# Sheet2.net
KiCad netlist of a schematic drawn in Altium Designer
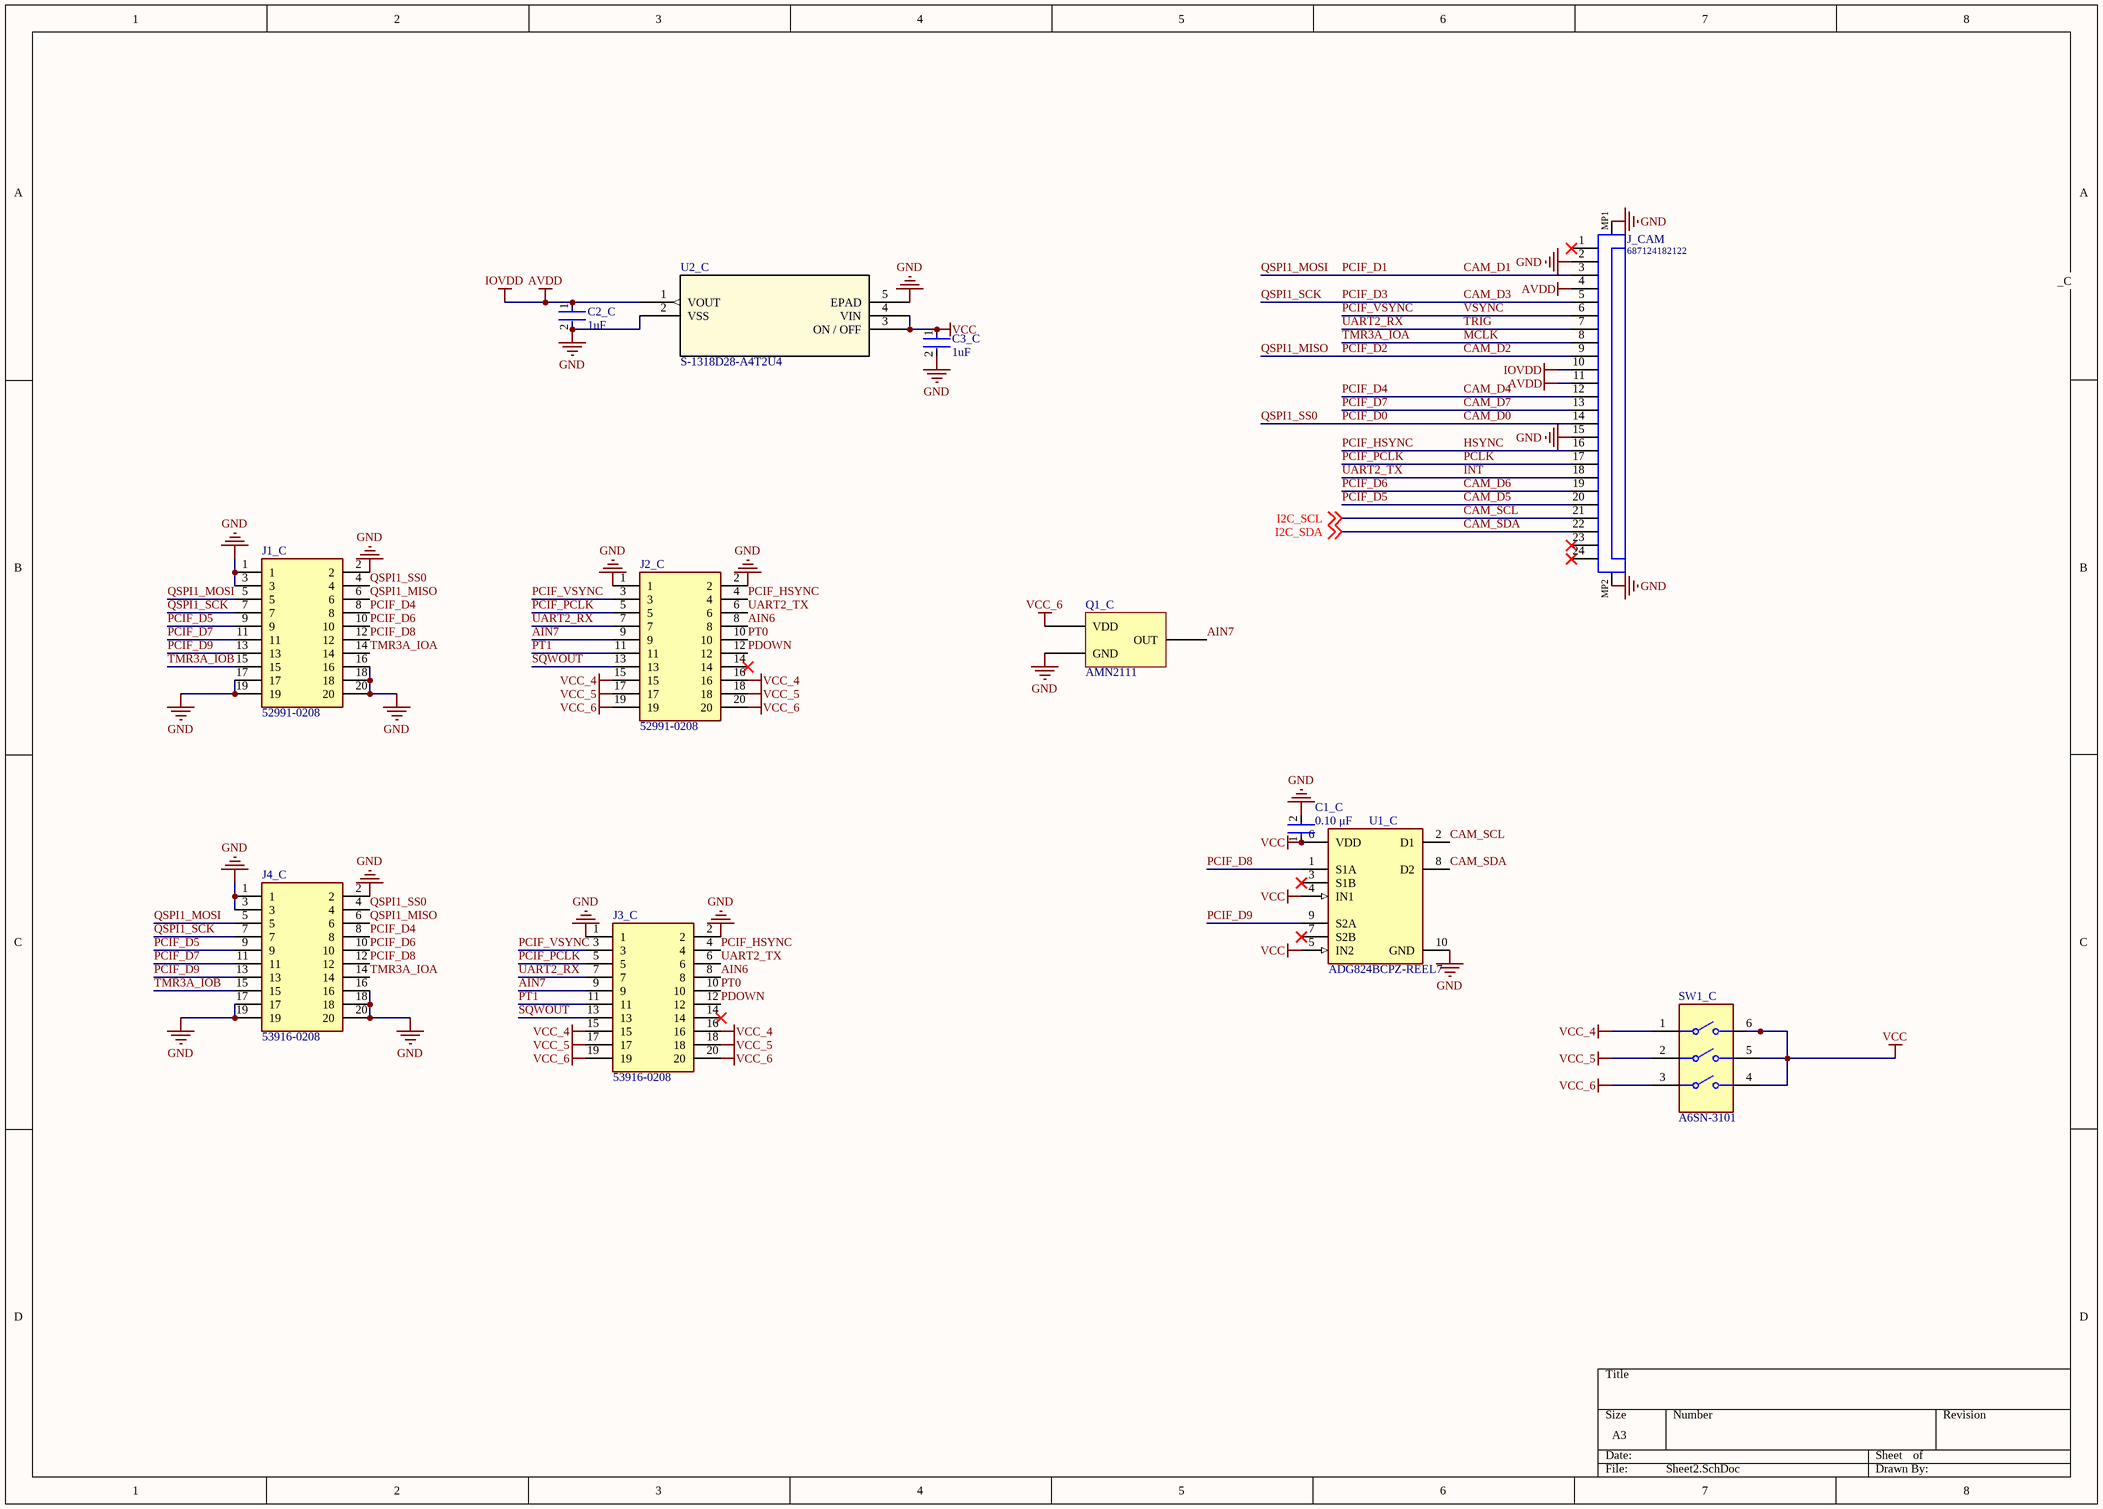
[diagram p0: Sheet2.SchDoc]

(export (version "E")
  (design (tool "Eeschema 10.0.6"))
  (components
    (comp (ref "C1_C")
      (value "C0402C104K8PACTU")
      (footprint "FP-C0402-BB-MFG")
      (description "CAP CER 0.1UF 10V X5R 0402")
      (fields
        (field (name "CAPACITANCE") "0.10 μF")
        (field (name "MANUFACTURER") "Kemet")
        (field (name "TOLERANCE") "0.1")
      )
      (libsource (lib "Altium Content Vault") (part "b4654b650e69147ec39a6b967a45e02"))
    )
    (comp (ref "C2_C")
      (value "UMK107BJ105KA-T")
      (footprint "FP-0603-L_1_6_0_1-W_0_8_0-IPC_A")
      (description "None")
      (fields (field (name "TOLERANCE") "10%") (field (name "CAPACITANCE") "1uF"))
      (libsource (lib "Altium Content Vault") (part "02cd4be3c70576c341d710602a673aa"))
    )
    (comp (ref "C3_C")
      (value "UMK107BJ105KA-T")
      (footprint "FP-0603-L_1_6_0_1-W_0_8_0-IPC_A")
      (description "None")
      (fields (field (name "TOLERANCE") "10%") (field (name "CAPACITANCE") "1uF"))
      (libsource (lib "Altium Content Vault") (part "02cd4be3c70576c341d710602a673aa"))
    )
    (comp (ref "J1_C")
      (value "52991-0208")
      (footprint "MOLEX_52991-0208")
      (description "20 Position Connector Receptacle, Center Strip Contacts Surface Mount Gold")
      (fields (field (name "MF") "Molex"))
      (libsource (lib "52991-0208") (part "52991-0208"))
    )
    (comp (ref "J2_C")
      (value "52991-0208")
      (footprint "MOLEX_52991-0208")
      (description "20 Position Connector Receptacle, Center Strip Contacts Surface Mount Gold")
      (fields (field (name "MF") "Molex"))
      (libsource (lib "52991-0208") (part "52991-0208"))
    )
    (comp (ref "J3_C")
      (value "53916-0208")
      (footprint "MOLEX-  539160208")
      (libsource (lib "52991-0208") (part "53916-0208"))
    )
    (comp (ref "J4_C")
      (value "53916-0208")
      (footprint "MOLEX-  539160208")
      (libsource (lib "52991-0208") (part "53916-0208"))
    )
    (comp (ref "J_CAM")
      (value "687124182122")
      (footprint "687124182122")
      (description "SMT ZIF Connectors WR-FPC, Horizontal, Back Locking Dual Contact, pitch 0.5 mm, 24 pins")
      (fields (field (name "MANUFACTURER") "Wurth Elektronik") (field (name "PUBLISHER") "WurthElektronik"))
      (libsource (lib "Altium Content Vault") (part "WE-6871241XXX22-24"))
    )
    (comp (ref "Q1_C")
      (value "AMN2111")
      (footprint "AMN21111")
      (libsource (lib "Integrated_Library1") (part "AMN2111"))
    )
    (comp (ref "SW1_C")
      (value "A6SN-3101")
      (footprint "FP-A6SN-3101-MFG")
      (description "SWITCH SLIDE DIP SPST 25MA 24V")
      (fields
        (field (name "MANUFACTURER") "Omron Electronics Inc-EMC Div")
        (field (name "OCTOPART") "https://octopart.com/a6sn-3101-omron-55396000")
      )
      (libsource (lib "Altium Content Vault") (part "c5ed29025a0a80be921a75429a93ff4"))
    )
    (comp (ref "U1_C")
      (value "ADG824BCPZ-REEL7")
      (footprint "FP-CP-10-10-MFG")
      (description "IC SWITCH DUAL SPDT 10LFCSP")
      (fields
        (field (name "OCTOPART") "https://octopart.com/adg824bcpz-reel7-analog+devices-12410880")
        (field (name "MANUFACTURER") "Analog Devices")
      )
      (libsource (lib "Altium Content Vault") (part "750f7653eda72c1ba3820f182f788e1"))
    )
    (comp (ref "U2_C")
      (value "S-1318D28-A4T2U4")
      (footprint "SMD04_HSNT_1X1_ABL")
      (description "No Description Available")
      (fields (field (name "COPYRIGHT") "Copyright (C) 2022 Ultra Librarian. All rights reserved."))
      (libsource (lib "S-1318D28-A4T2U4") (part "S-1318D28-A4T2U4"))
    )
  )
  (nets
    (net (code "1") (name "/AIN6") (class "Default")
      (node (ref "J2_C") (pin "8") (pinfunction "8_8") (pintype "passive"))
      (node (ref "J3_C") (pin "8") (pinfunction "8_8") (pintype "passive"))
    )
    (net (code "2") (name "/AIN7") (class "Default")
      (node (ref "J2_C") (pin "9") (pinfunction "9_9") (pintype "passive"))
      (node (ref "J3_C") (pin "9") (pinfunction "9_9") (pintype "passive"))
      (node (ref "Q1_C") (pin "3") (pinfunction "OUT_3") (pintype "passive"))
    )
    (net (code "3") (name "/CAM_D0") (class "Default")
      (node (ref "J1_C") (pin "4") (pinfunction "4_4") (pintype "passive"))
      (node (ref "J4_C") (pin "4") (pinfunction "4_4") (pintype "passive"))
      (node (ref "J_CAM") (pin "14") (pinfunction "14_14") (pintype "passive"))
    )
    (net (code "4") (name "/CAM_D1") (class "Default")
      (node (ref "J1_C") (pin "5") (pinfunction "5_5") (pintype "passive"))
      (node (ref "J4_C") (pin "5") (pinfunction "5_5") (pintype "passive"))
      (node (ref "J_CAM") (pin "3") (pinfunction "3_3") (pintype "passive"))
    )
    (net (code "5") (name "/CAM_D2") (class "Default")
      (node (ref "J1_C") (pin "6") (pinfunction "6_6") (pintype "passive"))
      (node (ref "J4_C") (pin "6") (pinfunction "6_6") (pintype "passive"))
      (node (ref "J_CAM") (pin "9") (pinfunction "9_9") (pintype "passive"))
    )
    (net (code "6") (name "/CAM_D3") (class "Default")
      (node (ref "J1_C") (pin "7") (pinfunction "7_7") (pintype "passive"))
      (node (ref "J4_C") (pin "7") (pinfunction "7_7") (pintype "passive"))
      (node (ref "J_CAM") (pin "5") (pinfunction "5_5") (pintype "passive"))
    )
    (net (code "7") (name "/CAM_D4") (class "Default")
      (node (ref "J1_C") (pin "8") (pinfunction "8_8") (pintype "passive"))
      (node (ref "J4_C") (pin "8") (pinfunction "8_8") (pintype "passive"))
      (node (ref "J_CAM") (pin "12") (pinfunction "12_12") (pintype "passive"))
    )
    (net (code "8") (name "/CAM_D5") (class "Default")
      (node (ref "J1_C") (pin "9") (pinfunction "9_9") (pintype "passive"))
      (node (ref "J4_C") (pin "9") (pinfunction "9_9") (pintype "passive"))
      (node (ref "J_CAM") (pin "20") (pinfunction "20_20") (pintype "passive"))
    )
    (net (code "9") (name "/CAM_D6") (class "Default")
      (node (ref "J1_C") (pin "10") (pinfunction "10_10") (pintype "passive"))
      (node (ref "J4_C") (pin "10") (pinfunction "10_10") (pintype "passive"))
      (node (ref "J_CAM") (pin "19") (pinfunction "19_19") (pintype "passive"))
    )
    (net (code "10") (name "/CAM_D7") (class "Default")
      (node (ref "J1_C") (pin "11") (pinfunction "11_11") (pintype "passive"))
      (node (ref "J4_C") (pin "11") (pinfunction "11_11") (pintype "passive"))
      (node (ref "J_CAM") (pin "13") (pinfunction "13_13") (pintype "passive"))
    )
    (net (code "11") (name "/HSYNC") (class "Default")
      (node (ref "J2_C") (pin "4") (pinfunction "4_4") (pintype "passive"))
      (node (ref "J3_C") (pin "4") (pinfunction "4_4") (pintype "passive"))
      (node (ref "J_CAM") (pin "16") (pinfunction "16_16") (pintype "passive"))
    )
    (net (code "12") (name "/INT") (class "Default")
      (node (ref "J2_C") (pin "6") (pinfunction "6_6") (pintype "passive"))
      (node (ref "J3_C") (pin "6") (pinfunction "6_6") (pintype "passive"))
      (node (ref "J_CAM") (pin "18") (pinfunction "18_18") (pintype "passive"))
    )
    (net (code "13") (name "/MCLK") (class "Default")
      (node (ref "J1_C") (pin "14") (pinfunction "14_14") (pintype "passive"))
      (node (ref "J4_C") (pin "14") (pinfunction "14_14") (pintype "passive"))
      (node (ref "J_CAM") (pin "8") (pinfunction "8_8") (pintype "passive"))
    )
    (net (code "14") (name "/PCIF_D8") (class "Default")
      (node (ref "J1_C") (pin "12") (pinfunction "12_12") (pintype "passive"))
      (node (ref "J4_C") (pin "12") (pinfunction "12_12") (pintype "passive"))
      (node (ref "U1_C") (pin "1") (pinfunction "S1A_1") (pintype "passive"))
    )
    (net (code "15") (name "/PCIF_D9") (class "Default")
      (node (ref "J1_C") (pin "13") (pinfunction "13_13") (pintype "passive"))
      (node (ref "J4_C") (pin "13") (pinfunction "13_13") (pintype "passive"))
      (node (ref "U1_C") (pin "9") (pinfunction "S2A_9") (pintype "passive"))
    )
    (net (code "16") (name "/PCIF_PCLK") (class "Default")
      (node (ref "J2_C") (pin "5") (pinfunction "5_5") (pintype "passive"))
      (node (ref "J3_C") (pin "5") (pinfunction "5_5") (pintype "passive"))
      (node (ref "J_CAM") (pin "17") (pinfunction "17_17") (pintype "passive"))
    )
    (net (code "17") (name "/PCIF_VSYNC") (class "Default")
      (node (ref "J2_C") (pin "3") (pinfunction "3_3") (pintype "passive"))
      (node (ref "J3_C") (pin "3") (pinfunction "3_3") (pintype "passive"))
      (node (ref "J_CAM") (pin "6") (pinfunction "6_6") (pintype "passive"))
    )
    (net (code "18") (name "/PDOWN") (class "Default")
      (node (ref "J2_C") (pin "12") (pinfunction "12_12") (pintype "passive"))
      (node (ref "J3_C") (pin "12") (pinfunction "12_12") (pintype "passive"))
    )
    (net (code "19") (name "/PT0") (class "Default")
      (node (ref "J2_C") (pin "10") (pinfunction "10_10") (pintype "passive"))
      (node (ref "J3_C") (pin "10") (pinfunction "10_10") (pintype "passive"))
    )
    (net (code "20") (name "/PT1") (class "Default")
      (node (ref "J2_C") (pin "11") (pinfunction "11_11") (pintype "passive"))
      (node (ref "J3_C") (pin "11") (pinfunction "11_11") (pintype "passive"))
    )
    (net (code "21") (name "/SQWOUT") (class "Default")
      (node (ref "J2_C") (pin "13") (pinfunction "13_13") (pintype "passive"))
      (node (ref "J3_C") (pin "13") (pinfunction "13_13") (pintype "passive"))
    )
    (net (code "22") (name "/TMR3A_IOB") (class "Default")
      (node (ref "J1_C") (pin "15") (pinfunction "15_15") (pintype "passive"))
      (node (ref "J4_C") (pin "15") (pinfunction "15_15") (pintype "passive"))
    )
    (net (code "23") (name "/TRIG") (class "Default")
      (node (ref "J2_C") (pin "7") (pinfunction "7_7") (pintype "passive"))
      (node (ref "J3_C") (pin "7") (pinfunction "7_7") (pintype "passive"))
      (node (ref "J_CAM") (pin "7") (pinfunction "7_7") (pintype "passive"))
    )
    (net (code "24") (name "AVDD") (class "Default")
      (node (ref "C2_C") (pin "1") (pinfunction "1_1") (pintype "passive"))
      (node (ref "J_CAM") (pin "10") (pinfunction "10_10") (pintype "passive"))
      (node (ref "J_CAM") (pin "11") (pinfunction "11_11") (pintype "passive"))
      (node (ref "J_CAM") (pin "4") (pinfunction "4_4") (pintype "passive"))
      (node (ref "U2_C") (pin "1") (pinfunction "VOUT_1") (pintype "output"))
    )
    (net (code "25") (name "GND") (class "Default")
      (node (ref "C1_C") (pin "2") (pinfunction "2_2") (pintype "passive"))
      (node (ref "C2_C") (pin "2") (pinfunction "2_2") (pintype "passive"))
      (node (ref "C3_C") (pin "2") (pinfunction "2_2") (pintype "passive"))
      (node (ref "J1_C") (pin "1") (pinfunction "1_1") (pintype "passive"))
      (node (ref "J1_C") (pin "16") (pinfunction "16_16") (pintype "passive"))
      (node (ref "J1_C") (pin "17") (pinfunction "17_17") (pintype "passive"))
      (node (ref "J1_C") (pin "18") (pinfunction "18_18") (pintype "passive"))
      (node (ref "J1_C") (pin "19") (pinfunction "19_19") (pintype "passive"))
      (node (ref "J1_C") (pin "2") (pinfunction "2_2") (pintype "passive"))
      (node (ref "J1_C") (pin "20") (pinfunction "20_20") (pintype "passive"))
      (node (ref "J1_C") (pin "3") (pinfunction "3_3") (pintype "passive"))
      (node (ref "J2_C") (pin "1") (pinfunction "1_1") (pintype "passive"))
      (node (ref "J2_C") (pin "2") (pinfunction "2_2") (pintype "passive"))
      (node (ref "J3_C") (pin "1") (pinfunction "1_1") (pintype "passive"))
      (node (ref "J3_C") (pin "2") (pinfunction "2_2") (pintype "passive"))
      (node (ref "J4_C") (pin "1") (pinfunction "1_1") (pintype "passive"))
      (node (ref "J4_C") (pin "16") (pinfunction "16_16") (pintype "passive"))
      (node (ref "J4_C") (pin "17") (pinfunction "17_17") (pintype "passive"))
      (node (ref "J4_C") (pin "18") (pinfunction "18_18") (pintype "passive"))
      (node (ref "J4_C") (pin "19") (pinfunction "19_19") (pintype "passive"))
      (node (ref "J4_C") (pin "2") (pinfunction "2_2") (pintype "passive"))
      (node (ref "J4_C") (pin "20") (pinfunction "20_20") (pintype "passive"))
      (node (ref "J4_C") (pin "3") (pinfunction "3_3") (pintype "passive"))
      (node (ref "J_CAM") (pin "15") (pinfunction "15_15") (pintype "passive"))
      (node (ref "J_CAM") (pin "2") (pinfunction "2_2") (pintype "passive"))
      (node (ref "J_CAM") (pin "MP1") (pinfunction "MP1_MP1") (pintype "passive"))
      (node (ref "J_CAM") (pin "MP2") (pinfunction "MP2_MP2") (pintype "passive"))
      (node (ref "Q1_C") (pin "2") (pinfunction "GND_2") (pintype "passive"))
      (node (ref "U1_C") (pin "10") (pinfunction "GND_10") (pintype "power_in"))
      (node (ref "U2_C") (pin "2") (pinfunction "VSS_2") (pintype "passive"))
      (node (ref "U2_C") (pin "5") (pinfunction "EPAD_5") (pintype "passive"))
    )
    (net (code "26") (name "I2C_SCL") (class "Default")
      (node (ref "J_CAM") (pin "21") (pinfunction "21_21") (pintype "passive"))
      (node (ref "U1_C") (pin "2") (pinfunction "D1_2") (pintype "passive"))
    )
    (net (code "27") (name "I2C_SDA") (class "Default")
      (node (ref "J_CAM") (pin "22") (pinfunction "22_22") (pintype "passive"))
      (node (ref "U1_C") (pin "8") (pinfunction "D2_8") (pintype "passive"))
    )
    (net (code "28") (name "VCC") (class "Default")
      (node (ref "C1_C") (pin "1") (pinfunction "1_1") (pintype "passive"))
      (node (ref "C3_C") (pin "1") (pinfunction "1_1") (pintype "passive"))
      (node (ref "SW1_C") (pin "4") (pinfunction "4_4") (pintype "passive"))
      (node (ref "SW1_C") (pin "5") (pinfunction "5_5") (pintype "passive"))
      (node (ref "SW1_C") (pin "6") (pinfunction "6_6") (pintype "passive"))
      (node (ref "U1_C") (pin "4") (pinfunction "IN1_4") (pintype "input"))
      (node (ref "U1_C") (pin "5") (pinfunction "IN2_5") (pintype "input"))
      (node (ref "U1_C") (pin "6") (pinfunction "VDD_6") (pintype "power_in"))
      (node (ref "U2_C") (pin "3") (pinfunction "ON_/_OFF_3") (pintype "passive"))
      (node (ref "U2_C") (pin "4") (pinfunction "VIN_4") (pintype "passive"))
    )
    (net (code "29") (name "VCC_4") (class "Default")
      (node (ref "J2_C") (pin "15") (pinfunction "15_15") (pintype "passive"))
      (node (ref "J2_C") (pin "16") (pinfunction "16_16") (pintype "passive"))
      (node (ref "J3_C") (pin "15") (pinfunction "15_15") (pintype "passive"))
      (node (ref "J3_C") (pin "16") (pinfunction "16_16") (pintype "passive"))
      (node (ref "SW1_C") (pin "1") (pinfunction "1_1") (pintype "passive"))
    )
    (net (code "30") (name "VCC_5") (class "Default")
      (node (ref "J2_C") (pin "17") (pinfunction "17_17") (pintype "passive"))
      (node (ref "J2_C") (pin "18") (pinfunction "18_18") (pintype "passive"))
      (node (ref "J3_C") (pin "17") (pinfunction "17_17") (pintype "passive"))
      (node (ref "J3_C") (pin "18") (pinfunction "18_18") (pintype "passive"))
      (node (ref "SW1_C") (pin "2") (pinfunction "2_2") (pintype "passive"))
    )
    (net (code "31") (name "VCC_6") (class "Default")
      (node (ref "J2_C") (pin "19") (pinfunction "19_19") (pintype "passive"))
      (node (ref "J2_C") (pin "20") (pinfunction "20_20") (pintype "passive"))
      (node (ref "J3_C") (pin "19") (pinfunction "19_19") (pintype "passive"))
      (node (ref "J3_C") (pin "20") (pinfunction "20_20") (pintype "passive"))
      (node (ref "Q1_C") (pin "1") (pinfunction "VDD_1") (pintype "passive"))
      (node (ref "SW1_C") (pin "3") (pinfunction "3_3") (pintype "passive"))
    )
    (net (code "32") (name "unconnected-(J2_C-Pad14)") (class "Default")
      (node (ref "J2_C") (pin "14") (pinfunction "14_14") (pintype "passive+no_connect"))
    )
    (net (code "33") (name "unconnected-(J3_C-Pad14)") (class "Default")
      (node (ref "J3_C") (pin "14") (pinfunction "14_14") (pintype "passive+no_connect"))
    )
    (net (code "34") (name "unconnected-(J_CAM-Pad1)") (class "Default")
      (node (ref "J_CAM") (pin "1") (pinfunction "1_1") (pintype "passive+no_connect"))
    )
    (net (code "35") (name "unconnected-(J_CAM-Pad23)") (class "Default")
      (node (ref "J_CAM") (pin "23") (pinfunction "23_23") (pintype "passive+no_connect"))
    )
    (net (code "36") (name "unconnected-(J_CAM-Pad24)") (class "Default")
      (node (ref "J_CAM") (pin "24") (pinfunction "24_24") (pintype "passive+no_connect"))
    )
    (net (code "37") (name "unconnected-(U1_C-S1B-Pad3)") (class "Default")
      (node (ref "U1_C") (pin "3") (pinfunction "S1B_3") (pintype "passive+no_connect"))
    )
    (net (code "38") (name "unconnected-(U1_C-S2B-Pad7)") (class "Default")
      (node (ref "U1_C") (pin "7") (pinfunction "S2B_7") (pintype "passive+no_connect"))
    )
  )
)
